# LV_project_1.net
KiCad netlist of a schematic drawn in Altium Designer
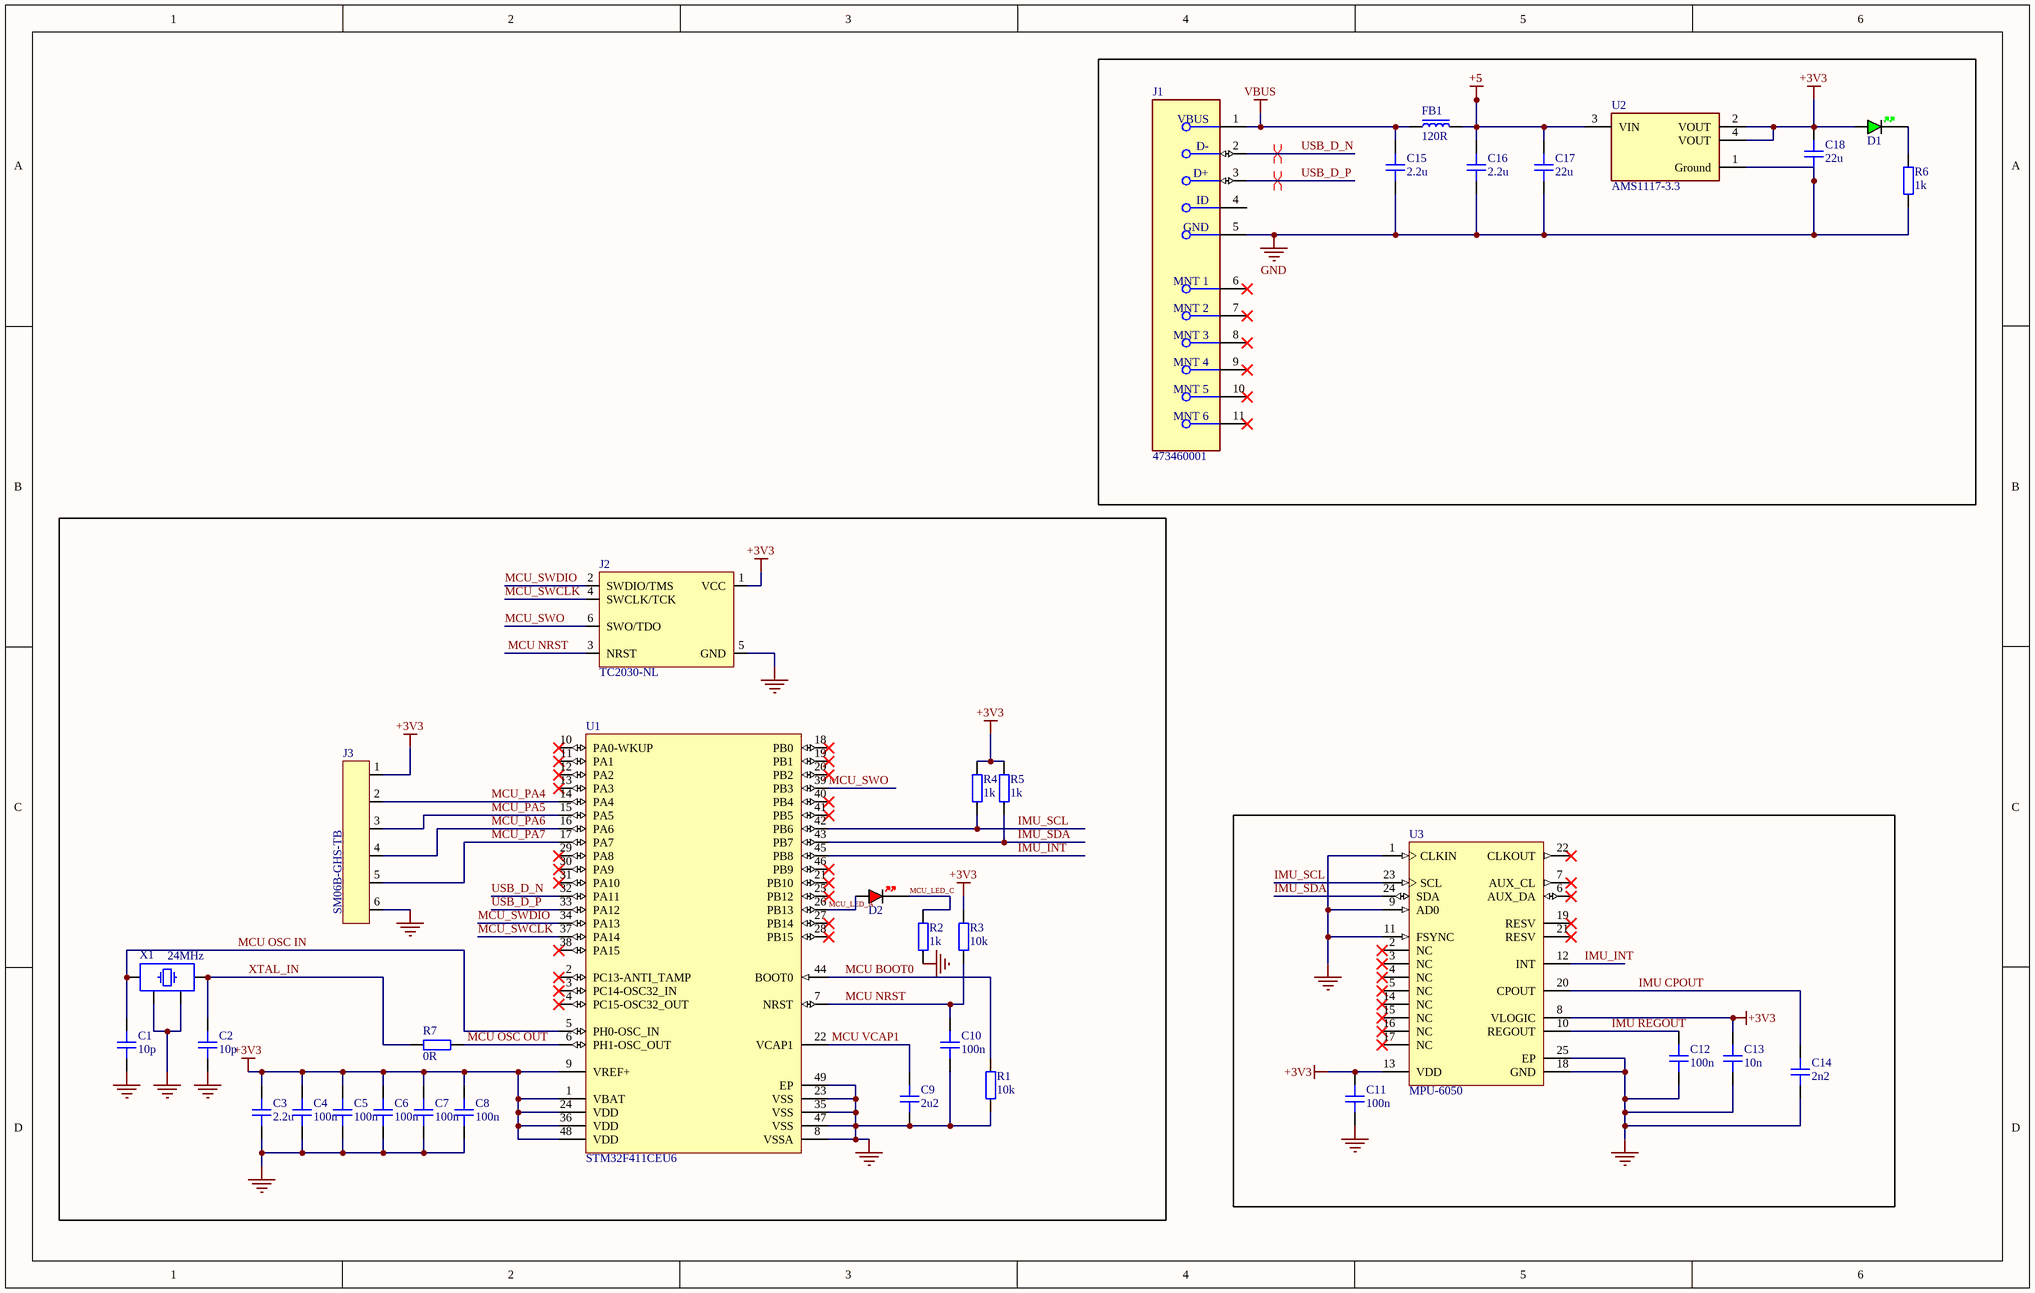
[diagram p0: LV project_1.SchDoc]

(export (version "E")
  (design (tool "Eeschema 10.0.6"))
  (components
    (comp (ref "C1")
      (value "10p")
      (footprint "CAP_0402")
      (description "Capacitor SMD 0402")
      (libsource (lib "Schematic-Lib-PhilsLab") (part "CAP_0402"))
    )
    (comp (ref "C2")
      (value "10p")
      (footprint "CAP_0402")
      (description "Capacitor SMD 0402")
      (libsource (lib "Schematic-Lib-PhilsLab") (part "CAP_0402"))
    )
    (comp (ref "C3")
      (value "2.2u")
      (footprint "CAP_0603")
      (description "Capacitor SMD 0603")
      (libsource (lib "Schematic-Lib-PhilsLab") (part "CAP_0603"))
    )
    (comp (ref "C4")
      (value "100n")
      (footprint "CAP_0402")
      (description "Capacitor SMD 0402")
      (libsource (lib "Schematic-Lib-PhilsLab") (part "CAP_0402"))
    )
    (comp (ref "C5")
      (value "100n")
      (footprint "CAP_0402")
      (description "Capacitor SMD 0402")
      (libsource (lib "Schematic-Lib-PhilsLab") (part "CAP_0402"))
    )
    (comp (ref "C6")
      (value "100n")
      (footprint "CAP_0402")
      (description "Capacitor SMD 0402")
      (libsource (lib "Schematic-Lib-PhilsLab") (part "CAP_0402"))
    )
    (comp (ref "C7")
      (value "100n")
      (footprint "CAP_0402")
      (description "Capacitor SMD 0402")
      (libsource (lib "Schematic-Lib-PhilsLab") (part "CAP_0402"))
    )
    (comp (ref "C8")
      (value "100n")
      (footprint "CAP_0402")
      (description "Capacitor SMD 0402")
      (libsource (lib "Schematic-Lib-PhilsLab") (part "CAP_0402"))
    )
    (comp (ref "C9")
      (value "2u2")
      (footprint "CAP_0603")
      (description "Capacitor SMD 0603")
      (libsource (lib "Schematic-Lib-PhilsLab") (part "CAP_0603"))
    )
    (comp (ref "C10")
      (value "100n")
      (footprint "CAP_0402")
      (description "Capacitor SMD 0402")
      (libsource (lib "Schematic-Lib-PhilsLab") (part "CAP_0402"))
    )
    (comp (ref "C11")
      (value "100n")
      (footprint "CAP_0402")
      (description "Capacitor SMD 0402")
      (libsource (lib "Schematic-Lib-PhilsLab") (part "CAP_0402"))
    )
    (comp (ref "C12")
      (value "100n")
      (footprint "CAP_0402")
      (description "Capacitor SMD 0402")
      (libsource (lib "Schematic-Lib-PhilsLab") (part "CAP_0402"))
    )
    (comp (ref "C13")
      (value "10n")
      (footprint "CAP_0402")
      (description "Capacitor SMD 0402")
      (libsource (lib "Schematic-Lib-PhilsLab") (part "CAP_0402"))
    )
    (comp (ref "C14")
      (value "2n2")
      (footprint "CAP_0402")
      (description "Capacitor SMD 0402")
      (libsource (lib "Schematic-Lib-PhilsLab") (part "CAP_0402"))
    )
    (comp (ref "C15")
      (value "2.2u")
      (footprint "CAP_0603")
      (description "Capacitor SMD 0603")
      (libsource (lib "Schematic-Lib-PhilsLab") (part "CAP_0603"))
    )
    (comp (ref "C16")
      (value "2.2u")
      (footprint "CAP_0603")
      (description "Capacitor SMD 0603")
      (libsource (lib "Schematic-Lib-PhilsLab") (part "CAP_0603"))
    )
    (comp (ref "C17")
      (value "22u")
      (footprint "CAP_0805")
      (description "Capacitor SMD 0805")
      (libsource (lib "Schematic-Lib-PhilsLab") (part "CAP_0805"))
    )
    (comp (ref "C18")
      (value "22u")
      (footprint "CAP_0805")
      (description "Capacitor SMD 0805")
      (libsource (lib "Schematic-Lib-PhilsLab") (part "CAP_0805"))
    )
    (comp (ref "D1")
      (value "GREEN")
      (footprint "LED_0402_GREEN")
      (description "LED 0402 GREEN SMD")
      (libsource (lib "Schematic-Lib-PhilsLab") (part "LED_0402_GREEN"))
    )
    (comp (ref "D2")
      (value "RED")
      (footprint "LED_0402_RED")
      (description "LED 0402 RED SMD")
      (libsource (lib "Schematic-Lib-PhilsLab") (part "LED_0402_RED"))
    )
    (comp (ref "FB1")
      (value "120R")
      (footprint "FB_0603")
      (description "Ferrite Bead SMD 0603")
      (libsource (lib "Schematic-Lib-PhilsLab") (part "FB_0603"))
    )
    (comp (ref "J1")
      (value "473460001")
      (footprint "FP-473460001-MFG")
      (description "USB - micro B USB 2.0 Receptacle Connector 5 Position Surface Mount, Right Angle")
      (fields (field (name "OCTOPART") "https://octopart.com/47346-0001-molex-7164928"))
      (libsource (lib "Altium Content Vault") (part "53ae1f1d9b557310b43ca686e5bb76a"))
    )
    (comp (ref "J2")
      (value "TC2030-NL")
      (footprint "TC2030-NL-FP")
      (description "Tag-Connect No-Solder SWD Debug Connector (No Legs) DO NOT PLACE")
      (fields
        (field (name "MANUFACTURER") "Tag-Connect")
        (field (name "MANUFACTURER PART NUMBER") "TC2030-NL-FP")
      )
      (libsource (lib "Schematic-Lib-PhilsLab") (part "TC2030-NL"))
    )
    (comp (ref "J3")
      (value "SM06B-GHS-TB")
      (footprint "SM06B-GHS-TB")
      (description "Header Connector 6 Position 1.25MM Pitch SMD Horizontal JST GH")
      (fields (field (name "MANUFACTURER") "JST"))
      (libsource (lib "Schematic-Lib-PhilsLab") (part "SM06B-GHS-TB"))
    )
    (comp (ref "R1")
      (value "10k")
      (footprint "RES_0402")
      (description "Resistor SMD 0402")
      (libsource (lib "Schematic-Lib-PhilsLab") (part "RES_0402"))
    )
    (comp (ref "R2")
      (value "1k")
      (footprint "RES_0402")
      (description "Resistor SMD 0402")
      (libsource (lib "Schematic-Lib-PhilsLab") (part "RES_0402"))
    )
    (comp (ref "R3")
      (value "10k")
      (footprint "RES_0402")
      (description "Resistor SMD 0402")
      (libsource (lib "Schematic-Lib-PhilsLab") (part "RES_0402"))
    )
    (comp (ref "R4")
      (value "1k")
      (footprint "RES_0402")
      (description "Resistor SMD 0402")
      (libsource (lib "Schematic-Lib-PhilsLab") (part "RES_0402"))
    )
    (comp (ref "R5")
      (value "1k")
      (footprint "RES_0402")
      (description "Resistor SMD 0402")
      (libsource (lib "Schematic-Lib-PhilsLab") (part "RES_0402"))
    )
    (comp (ref "R6")
      (value "1k")
      (footprint "RES_0402")
      (description "Resistor SMD 0402")
      (libsource (lib "Schematic-Lib-PhilsLab") (part "RES_0402"))
    )
    (comp (ref "R7")
      (value "0R")
      (footprint "RES_0402")
      (description "Resistor SMD 0402")
      (libsource (lib "Schematic-Lib-PhilsLab") (part "RES_0402"))
    )
    (comp (ref "U1")
      (value "STM32F411CEU6")
      (footprint "STM-UFQFPN48_L")
      (libsource (lib "Altium Content Vault") (part "MC-ARM-STM32F411-UFQFPN48"))
    )
    (comp (ref "U2")
      (value "AMS1117-3.3")
      (footprint "FP-AMS1117-IPC_C")
      (description "LDO Voltage Regulators 1A, 3.3V")
      (fields
        (field (name "OCTOPART") "https://octopart.com/ams1117-3.3-advanced+monolithic+systems-25899300")
        (field (name "MANUFACTURER") "Advanced Monolithic Systems")
      )
      (libsource (lib "Altium Content Vault") (part "8bdbb5f8e77002000e30dd2845d0354"))
    )
    (comp (ref "U3")
      (value "MPU-6050")
      (footprint "IS-QFN-24_V")
      (fields (field (name "MANUFACTURER") "InvenSense"))
      (libsource (lib "Altium Content Vault") (part "IS-MPU-6050-QFN-24"))
    )
    (comp (ref "X1")
      (value "24MHz")
      (footprint "XTAL_3225")
      (description "Crystal SMD 24MHz 10PPM 7pF 3225")
      (fields
        (field (name "MANUFACTURER") "Epson")
        (field (name "MANUFACTURER PART NUMBER") "TSX-3225 24.0000MF15X-AC")
      )
      (libsource (lib "Schematic-Lib-PhilsLab") (part "TSX-3225_24.0000MF15X-AC"))
    )
  )
  (nets
    (net (code "1") (name "+3V3") (class "Default")
      (node (ref "C11") (pin "2") (pinfunction "2_2") (pintype "passive"))
      (node (ref "C13") (pin "2") (pinfunction "2_2") (pintype "passive"))
      (node (ref "C18") (pin "2") (pinfunction "2_2") (pintype "passive"))
      (node (ref "C3") (pin "2") (pinfunction "2_2") (pintype "passive"))
      (node (ref "C4") (pin "2") (pinfunction "2_2") (pintype "passive"))
      (node (ref "C5") (pin "2") (pinfunction "2_2") (pintype "passive"))
      (node (ref "C6") (pin "2") (pinfunction "2_2") (pintype "passive"))
      (node (ref "C7") (pin "2") (pinfunction "2_2") (pintype "passive"))
      (node (ref "C8") (pin "2") (pinfunction "2_2") (pintype "passive"))
      (node (ref "D1") (pin "A") (pinfunction "A_A") (pintype "passive"))
      (node (ref "J2") (pin "1") (pinfunction "VCC_1") (pintype "passive"))
      (node (ref "J3") (pin "1") (pinfunction "1_1") (pintype "passive"))
      (node (ref "R3") (pin "2") (pinfunction "2_2") (pintype "passive"))
      (node (ref "R4") (pin "1") (pinfunction "1_1") (pintype "passive"))
      (node (ref "R5") (pin "1") (pinfunction "1_1") (pintype "passive"))
      (node (ref "U1") (pin "1") (pinfunction "VBAT_1") (pintype "power_in"))
      (node (ref "U1") (pin "24") (pinfunction "VDD_24") (pintype "power_in"))
      (node (ref "U1") (pin "36") (pinfunction "VDD_36") (pintype "power_in"))
      (node (ref "U1") (pin "48") (pinfunction "VDD_48") (pintype "power_in"))
      (node (ref "U1") (pin "9") (pinfunction "VREF+_9") (pintype "power_in"))
      (node (ref "U2") (pin "2") (pinfunction "VOUT_2") (pintype "passive"))
      (node (ref "U2") (pin "4") (pinfunction "VOUT_4") (pintype "passive"))
      (node (ref "U3") (pin "13") (pinfunction "VDD_13") (pintype "power_in"))
      (node (ref "U3") (pin "8") (pinfunction "VLOGIC_8") (pintype "power_in"))
    )
    (net (code "2") (name "+5") (class "Default")
      (node (ref "C16") (pin "2") (pinfunction "2_2") (pintype "passive"))
      (node (ref "C17") (pin "2") (pinfunction "2_2") (pintype "passive"))
      (node (ref "FB1") (pin "2") (pinfunction "2_2") (pintype "passive"))
      (node (ref "U2") (pin "3") (pinfunction "VIN_3") (pintype "power_in"))
    )
    (net (code "3") (name "/ MCU BOOT0") (class "Default")
      (node (ref "R1") (pin "2") (pinfunction "2_2") (pintype "passive"))
      (node (ref "U1") (pin "44") (pinfunction "BOOT0_44") (pintype "input"))
    )
    (net (code "4") (name "/ MCU NRST") (class "Default")
      (node (ref "C10") (pin "2") (pinfunction "2_2") (pintype "passive"))
      (node (ref "J2") (pin "3") (pinfunction "NRST_3") (pintype "passive"))
      (node (ref "R3") (pin "1") (pinfunction "1_1") (pintype "passive"))
      (node (ref "U1") (pin "7") (pinfunction "NRST_7") (pintype "bidirectional"))
    )
    (net (code "5") (name "/ MCU OSC IN") (class "Default")
      (node (ref "C1") (pin "2") (pinfunction "2_2") (pintype "passive"))
      (node (ref "U1") (pin "5") (pinfunction "PH0-OSC_IN_5") (pintype "bidirectional"))
      (node (ref "X1") (pin "1") (pinfunction "1_1") (pintype "passive"))
    )
    (net (code "6") (name "/ MCU OSC OUT") (class "Default")
      (node (ref "R7") (pin "1") (pinfunction "1_1") (pintype "passive"))
      (node (ref "U1") (pin "6") (pinfunction "PH1-OSC_OUT_6") (pintype "bidirectional"))
    )
    (net (code "7") (name "/ MCU VCAP1") (class "Default")
      (node (ref "C9") (pin "2") (pinfunction "2_2") (pintype "passive"))
      (node (ref "U1") (pin "22") (pinfunction "VCAP1_22") (pintype "passive"))
    )
    (net (code "8") (name "/IMU CPOUT") (class "Default")
      (node (ref "C14") (pin "2") (pinfunction "2_2") (pintype "passive"))
      (node (ref "U3") (pin "20") (pinfunction "CPOUT_20") (pintype "passive"))
    )
    (net (code "9") (name "/IMU REGOUT") (class "Default")
      (node (ref "C12") (pin "2") (pinfunction "2_2") (pintype "passive"))
      (node (ref "U3") (pin "10") (pinfunction "REGOUT_10") (pintype "passive"))
    )
    (net (code "10") (name "/IMU_INT") (class "Default")
      (node (ref "U1") (pin "45") (pinfunction "PB8_45") (pintype "bidirectional"))
      (node (ref "U3") (pin "12") (pinfunction "INT_12") (pintype "open_collector"))
    )
    (net (code "11") (name "/IMU_SCL") (class "Default")
      (node (ref "R4") (pin "2") (pinfunction "2_2") (pintype "passive"))
      (node (ref "U1") (pin "42") (pinfunction "PB6_42") (pintype "bidirectional"))
      (node (ref "U3") (pin "23") (pinfunction "SCL_23") (pintype "input"))
    )
    (net (code "12") (name "/IMU_SDA") (class "Default")
      (node (ref "R5") (pin "2") (pinfunction "2_2") (pintype "passive"))
      (node (ref "U1") (pin "43") (pinfunction "PB7_43") (pintype "bidirectional"))
      (node (ref "U3") (pin "24") (pinfunction "SDA_24") (pintype "bidirectional"))
    )
    (net (code "13") (name "/MCU_LED_A") (class "Default")
      (node (ref "D2") (pin "A") (pinfunction "A_A") (pintype "passive"))
      (node (ref "U1") (pin "26") (pinfunction "PB13_26") (pintype "bidirectional"))
    )
    (net (code "14") (name "/MCU_LED_C") (class "Default")
      (node (ref "D2") (pin "K") (pinfunction "K_K") (pintype "passive"))
      (node (ref "R2") (pin "1") (pinfunction "1_1") (pintype "passive"))
    )
    (net (code "15") (name "/MCU_PA4") (class "Default")
      (node (ref "J3") (pin "2") (pinfunction "2_2") (pintype "passive"))
      (node (ref "U1") (pin "14") (pinfunction "PA4_14") (pintype "bidirectional"))
    )
    (net (code "16") (name "/MCU_PA5") (class "Default")
      (node (ref "J3") (pin "3") (pinfunction "3_3") (pintype "passive"))
      (node (ref "U1") (pin "15") (pinfunction "PA5_15") (pintype "bidirectional"))
    )
    (net (code "17") (name "/MCU_PA6") (class "Default")
      (node (ref "J3") (pin "4") (pinfunction "4_4") (pintype "passive"))
      (node (ref "U1") (pin "16") (pinfunction "PA6_16") (pintype "bidirectional"))
    )
    (net (code "18") (name "/MCU_PA7") (class "Default")
      (node (ref "J3") (pin "5") (pinfunction "5_5") (pintype "passive"))
      (node (ref "U1") (pin "17") (pinfunction "PA7_17") (pintype "bidirectional"))
    )
    (net (code "19") (name "/MCU_SWCLK") (class "Default")
      (node (ref "J2") (pin "4") (pinfunction "SWCLK/TCK_4") (pintype "passive"))
      (node (ref "U1") (pin "37") (pinfunction "PA14_37") (pintype "bidirectional"))
    )
    (net (code "20") (name "/MCU_SWDIO") (class "Default")
      (node (ref "J2") (pin "2") (pinfunction "SWDIO/TMS_2") (pintype "passive"))
      (node (ref "U1") (pin "34") (pinfunction "PA13_34") (pintype "bidirectional"))
    )
    (net (code "21") (name "/MCU_SWO") (class "Default")
      (node (ref "J2") (pin "6") (pinfunction "SWO/TDO_6") (pintype "passive"))
      (node (ref "U1") (pin "39") (pinfunction "PB3_39") (pintype "bidirectional"))
    )
    (net (code "22") (name "/USB_D_N") (class "Default")
      (node (ref "J1") (pin "2") (pinfunction "D-_2") (pintype "bidirectional"))
      (node (ref "U1") (pin "32") (pinfunction "PA11_32") (pintype "bidirectional"))
    )
    (net (code "23") (name "/USB_D_P") (class "Default")
      (node (ref "J1") (pin "3") (pinfunction "D+_3") (pintype "bidirectional"))
      (node (ref "U1") (pin "33") (pinfunction "PA12_33") (pintype "bidirectional"))
    )
    (net (code "24") (name "/XTAL_IN") (class "Default")
      (node (ref "C2") (pin "2") (pinfunction "2_2") (pintype "passive"))
      (node (ref "R7") (pin "2") (pinfunction "2_2") (pintype "passive"))
      (node (ref "X1") (pin "3") (pinfunction "3_3") (pintype "passive"))
    )
    (net (code "25") (name "GND") (class "Default")
      (node (ref "C1") (pin "1") (pinfunction "1_1") (pintype "passive"))
      (node (ref "C10") (pin "1") (pinfunction "1_1") (pintype "passive"))
      (node (ref "C11") (pin "1") (pinfunction "1_1") (pintype "passive"))
      (node (ref "C12") (pin "1") (pinfunction "1_1") (pintype "passive"))
      (node (ref "C13") (pin "1") (pinfunction "1_1") (pintype "passive"))
      (node (ref "C14") (pin "1") (pinfunction "1_1") (pintype "passive"))
      (node (ref "C15") (pin "1") (pinfunction "1_1") (pintype "passive"))
      (node (ref "C16") (pin "1") (pinfunction "1_1") (pintype "passive"))
      (node (ref "C17") (pin "1") (pinfunction "1_1") (pintype "passive"))
      (node (ref "C18") (pin "1") (pinfunction "1_1") (pintype "passive"))
      (node (ref "C2") (pin "1") (pinfunction "1_1") (pintype "passive"))
      (node (ref "C3") (pin "1") (pinfunction "1_1") (pintype "passive"))
      (node (ref "C4") (pin "1") (pinfunction "1_1") (pintype "passive"))
      (node (ref "C5") (pin "1") (pinfunction "1_1") (pintype "passive"))
      (node (ref "C6") (pin "1") (pinfunction "1_1") (pintype "passive"))
      (node (ref "C7") (pin "1") (pinfunction "1_1") (pintype "passive"))
      (node (ref "C8") (pin "1") (pinfunction "1_1") (pintype "passive"))
      (node (ref "C9") (pin "1") (pinfunction "1_1") (pintype "passive"))
      (node (ref "J1") (pin "5") (pinfunction "GND_5") (pintype "power_in"))
      (node (ref "J2") (pin "5") (pinfunction "GND_5") (pintype "passive"))
      (node (ref "J3") (pin "6") (pinfunction "6_6") (pintype "passive"))
      (node (ref "R1") (pin "1") (pinfunction "1_1") (pintype "passive"))
      (node (ref "R2") (pin "2") (pinfunction "2_2") (pintype "passive"))
      (node (ref "R6") (pin "1") (pinfunction "1_1") (pintype "passive"))
      (node (ref "U1") (pin "23") (pinfunction "VSS_23") (pintype "power_in"))
      (node (ref "U1") (pin "35") (pinfunction "VSS_35") (pintype "power_in"))
      (node (ref "U1") (pin "47") (pinfunction "VSS_47") (pintype "power_in"))
      (node (ref "U1") (pin "49") (pinfunction "EP_49") (pintype "power_in"))
      (node (ref "U1") (pin "8") (pinfunction "VSSA_8") (pintype "power_in"))
      (node (ref "U2") (pin "1") (pinfunction "Ground_1") (pintype "power_in"))
      (node (ref "U3") (pin "1") (pinfunction "CLKIN_1") (pintype "input"))
      (node (ref "U3") (pin "11") (pinfunction "FSYNC_11") (pintype "input"))
      (node (ref "U3") (pin "18") (pinfunction "GND_18") (pintype "power_in"))
      (node (ref "U3") (pin "25") (pinfunction "EP_25") (pintype "power_in"))
      (node (ref "U3") (pin "9") (pinfunction "AD0_9") (pintype "input"))
      (node (ref "X1") (pin "2") (pinfunction "2_2") (pintype "passive"))
      (node (ref "X1") (pin "4") (pinfunction "4_4") (pintype "passive"))
    )
    (net (code "26") (name "Net-(D1-PadK)") (class "Default")
      (node (ref "D1") (pin "K") (pinfunction "K_K") (pintype "passive"))
      (node (ref "R6") (pin "2") (pinfunction "2_2") (pintype "passive"))
    )
    (net (code "27") (name "VBUS") (class "Default")
      (node (ref "C15") (pin "2") (pinfunction "2_2") (pintype "passive"))
      (node (ref "FB1") (pin "1") (pinfunction "1_1") (pintype "passive"))
      (node (ref "J1") (pin "1") (pinfunction "VBUS_1") (pintype "power_in"))
    )
    (net (code "28") (name "unconnected-(J1-ID-Pad4)") (class "Default")
      (node (ref "J1") (pin "4") (pinfunction "ID_4") (pintype "passive"))
    )
    (net (code "29") (name "unconnected-(J1-MNT_1-Pad6)") (class "Default")
      (node (ref "J1") (pin "6") (pinfunction "MNT_1_6") (pintype "passive+no_connect"))
    )
    (net (code "30") (name "unconnected-(J1-MNT_2-Pad7)") (class "Default")
      (node (ref "J1") (pin "7") (pinfunction "MNT_2_7") (pintype "passive+no_connect"))
    )
    (net (code "31") (name "unconnected-(J1-MNT_3-Pad8)") (class "Default")
      (node (ref "J1") (pin "8") (pinfunction "MNT_3_8") (pintype "passive+no_connect"))
    )
    (net (code "32") (name "unconnected-(J1-MNT_4-Pad9)") (class "Default")
      (node (ref "J1") (pin "9") (pinfunction "MNT_4_9") (pintype "passive+no_connect"))
    )
    (net (code "33") (name "unconnected-(J1-MNT_5-Pad10)") (class "Default")
      (node (ref "J1") (pin "10") (pinfunction "MNT_5_10") (pintype "passive+no_connect"))
    )
    (net (code "34") (name "unconnected-(J1-MNT_6-Pad11)") (class "Default")
      (node (ref "J1") (pin "11") (pinfunction "MNT_6_11") (pintype "passive+no_connect"))
    )
    (net (code "35") (name "unconnected-(U1-PA0-WKUP-Pad10)") (class "Default")
      (node (ref "U1") (pin "10") (pinfunction "PA0-WKUP_10") (pintype "bidirectional+no_connect"))
    )
    (net (code "36") (name "unconnected-(U1-PA1-Pad11)") (class "Default")
      (node (ref "U1") (pin "11") (pinfunction "PA1_11") (pintype "bidirectional+no_connect"))
    )
    (net (code "37") (name "unconnected-(U1-PA2-Pad12)") (class "Default")
      (node (ref "U1") (pin "12") (pinfunction "PA2_12") (pintype "bidirectional+no_connect"))
    )
    (net (code "38") (name "unconnected-(U1-PA3-Pad13)") (class "Default")
      (node (ref "U1") (pin "13") (pinfunction "PA3_13") (pintype "bidirectional+no_connect"))
    )
    (net (code "39") (name "unconnected-(U1-PA8-Pad29)") (class "Default")
      (node (ref "U1") (pin "29") (pinfunction "PA8_29") (pintype "bidirectional+no_connect"))
    )
    (net (code "40") (name "unconnected-(U1-PA9-Pad30)") (class "Default")
      (node (ref "U1") (pin "30") (pinfunction "PA9_30") (pintype "bidirectional+no_connect"))
    )
    (net (code "41") (name "unconnected-(U1-PA10-Pad31)") (class "Default")
      (node (ref "U1") (pin "31") (pinfunction "PA10_31") (pintype "bidirectional+no_connect"))
    )
    (net (code "42") (name "unconnected-(U1-PA15-Pad38)") (class "Default")
      (node (ref "U1") (pin "38") (pinfunction "PA15_38") (pintype "bidirectional+no_connect"))
    )
    (net (code "43") (name "unconnected-(U1-PB0-Pad18)") (class "Default")
      (node (ref "U1") (pin "18") (pinfunction "PB0_18") (pintype "bidirectional+no_connect"))
    )
    (net (code "44") (name "unconnected-(U1-PB1-Pad19)") (class "Default")
      (node (ref "U1") (pin "19") (pinfunction "PB1_19") (pintype "bidirectional+no_connect"))
    )
    (net (code "45") (name "unconnected-(U1-PB2-Pad20)") (class "Default")
      (node (ref "U1") (pin "20") (pinfunction "PB2_20") (pintype "bidirectional+no_connect"))
    )
    (net (code "46") (name "unconnected-(U1-PB4-Pad40)") (class "Default")
      (node (ref "U1") (pin "40") (pinfunction "PB4_40") (pintype "bidirectional+no_connect"))
    )
    (net (code "47") (name "unconnected-(U1-PB5-Pad41)") (class "Default")
      (node (ref "U1") (pin "41") (pinfunction "PB5_41") (pintype "bidirectional+no_connect"))
    )
    (net (code "48") (name "unconnected-(U1-PB9-Pad46)") (class "Default")
      (node (ref "U1") (pin "46") (pinfunction "PB9_46") (pintype "bidirectional+no_connect"))
    )
    (net (code "49") (name "unconnected-(U1-PB10-Pad21)") (class "Default")
      (node (ref "U1") (pin "21") (pinfunction "PB10_21") (pintype "bidirectional+no_connect"))
    )
    (net (code "50") (name "unconnected-(U1-PB12-Pad25)") (class "Default")
      (node (ref "U1") (pin "25") (pinfunction "PB12_25") (pintype "bidirectional+no_connect"))
    )
    (net (code "51") (name "unconnected-(U1-PB14-Pad27)") (class "Default")
      (node (ref "U1") (pin "27") (pinfunction "PB14_27") (pintype "bidirectional+no_connect"))
    )
    (net (code "52") (name "unconnected-(U1-PB15-Pad28)") (class "Default")
      (node (ref "U1") (pin "28") (pinfunction "PB15_28") (pintype "bidirectional+no_connect"))
    )
    (net (code "53") (name "unconnected-(U1-PC13-ANTI_TAMP-Pad2)") (class "Default")
      (node (ref "U1") (pin "2") (pinfunction "PC13-ANTI_TAMP_2") (pintype "bidirectional+no_connect"))
    )
    (net (code "54") (name "unconnected-(U1-PC14-OSC32_IN-Pad3)") (class "Default")
      (node (ref "U1") (pin "3") (pinfunction "PC14-OSC32_IN_3") (pintype "bidirectional+no_connect"))
    )
    (net (code "55") (name "unconnected-(U1-PC15-OSC32_OUT-Pad4)") (class "Default")
      (node (ref "U1") (pin "4") (pinfunction "PC15-OSC32_OUT_4") (pintype "bidirectional+no_connect"))
    )
    (net (code "56") (name "unconnected-(U3-AUX_CL-Pad7)") (class "Default")
      (node (ref "U3") (pin "7") (pinfunction "AUX_CL_7") (pintype "output+no_connect"))
    )
    (net (code "57") (name "unconnected-(U3-AUX_DA-Pad6)") (class "Default")
      (node (ref "U3") (pin "6") (pinfunction "AUX_DA_6") (pintype "bidirectional+no_connect"))
    )
    (net (code "58") (name "unconnected-(U3-CLKOUT-Pad22)") (class "Default")
      (node (ref "U3") (pin "22") (pinfunction "CLKOUT_22") (pintype "output+no_connect"))
    )
    (net (code "59") (name "unconnected-(U3-NC-Pad2)") (class "Default")
      (node (ref "U3") (pin "2") (pinfunction "NC_2") (pintype "passive+no_connect"))
    )
    (net (code "60") (name "unconnected-(U3-NC-Pad3)") (class "Default")
      (node (ref "U3") (pin "3") (pinfunction "NC_3") (pintype "passive+no_connect"))
    )
    (net (code "61") (name "unconnected-(U3-NC-Pad4)") (class "Default")
      (node (ref "U3") (pin "4") (pinfunction "NC_4") (pintype "passive+no_connect"))
    )
    (net (code "62") (name "unconnected-(U3-NC-Pad5)") (class "Default")
      (node (ref "U3") (pin "5") (pinfunction "NC_5") (pintype "passive+no_connect"))
    )
    (net (code "63") (name "unconnected-(U3-NC-Pad14)") (class "Default")
      (node (ref "U3") (pin "14") (pinfunction "NC_14") (pintype "passive+no_connect"))
    )
    (net (code "64") (name "unconnected-(U3-NC-Pad15)") (class "Default")
      (node (ref "U3") (pin "15") (pinfunction "NC_15") (pintype "passive+no_connect"))
    )
    (net (code "65") (name "unconnected-(U3-NC-Pad16)") (class "Default")
      (node (ref "U3") (pin "16") (pinfunction "NC_16") (pintype "passive+no_connect"))
    )
    (net (code "66") (name "unconnected-(U3-NC-Pad17)") (class "Default")
      (node (ref "U3") (pin "17") (pinfunction "NC_17") (pintype "passive+no_connect"))
    )
    (net (code "67") (name "unconnected-(U3-RESV-Pad19)") (class "Default")
      (node (ref "U3") (pin "19") (pinfunction "RESV_19") (pintype "passive+no_connect"))
    )
    (net (code "68") (name "unconnected-(U3-RESV-Pad21)") (class "Default")
      (node (ref "U3") (pin "21") (pinfunction "RESV_21") (pintype "passive+no_connect"))
    )
  )
)
